# M220C.net
KiCad netlist of a schematic drawn in EAGLE
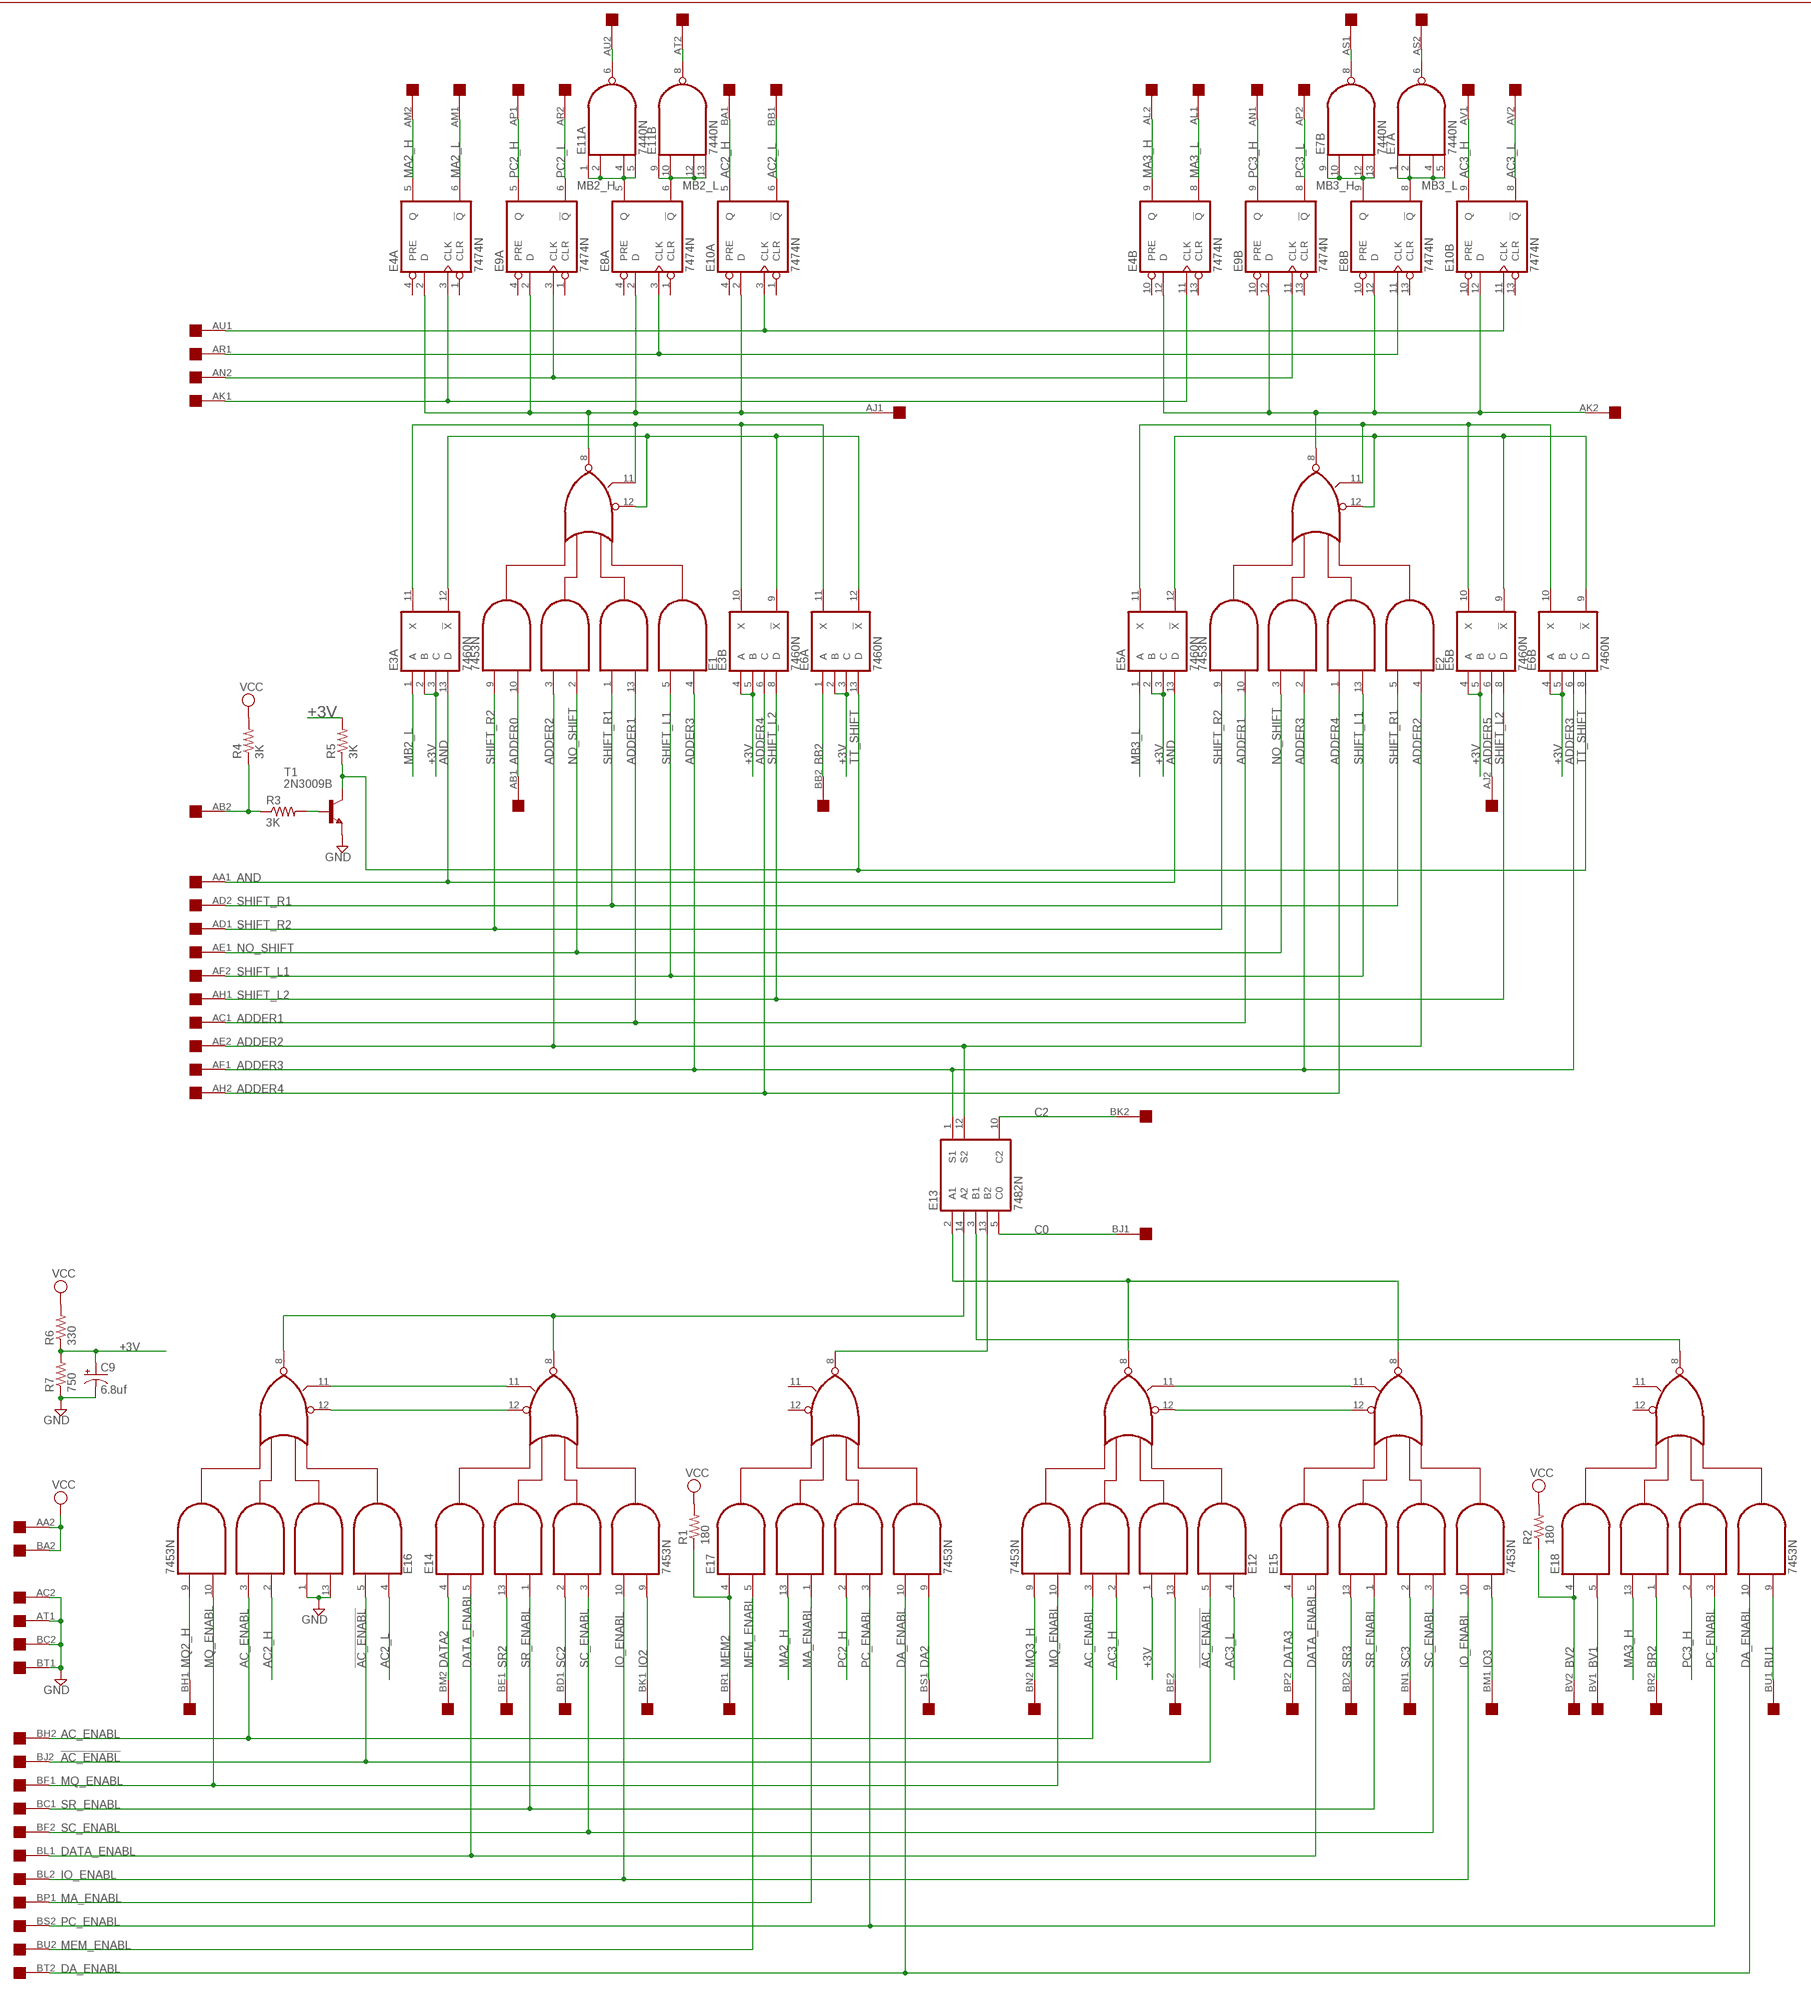
[diagram p0: schematic, sheet 1, part 1 of 2]
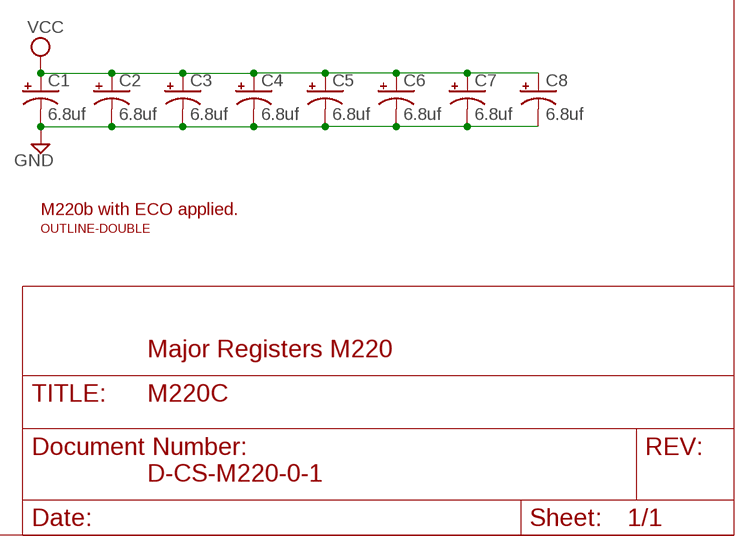
[diagram p1: schematic, sheet 1, part 2 of 2]

(export (version "E")
  (design (tool "Eeschema 10.0.6"))
  (components
    (comp (ref "C1")
      (value "6.8uf")
      (footprint "eagle-import:E15-5")
      (libsource (lib "eagle-import") (part "CPOL-USE15-5AXIAL"))
    )
    (comp (ref "C2")
      (value "6.8uf")
      (footprint "eagle-import:E15-5")
      (libsource (lib "eagle-import") (part "CPOL-USE15-5AXIAL"))
    )
    (comp (ref "C3")
      (value "6.8uf")
      (footprint "eagle-import:E15-5")
      (libsource (lib "eagle-import") (part "CPOL-USE15-5AXIAL"))
    )
    (comp (ref "C4")
      (value "6.8uf")
      (footprint "eagle-import:E15-5")
      (libsource (lib "eagle-import") (part "CPOL-USE15-5AXIAL"))
    )
    (comp (ref "C5")
      (value "6.8uf")
      (footprint "eagle-import:E15-5")
      (libsource (lib "eagle-import") (part "CPOL-USE15-5AXIAL"))
    )
    (comp (ref "C6")
      (value "6.8uf")
      (footprint "eagle-import:E15-5")
      (libsource (lib "eagle-import") (part "CPOL-USE15-5AXIAL"))
    )
    (comp (ref "C7")
      (value "6.8uf")
      (footprint "eagle-import:E15-5")
      (libsource (lib "eagle-import") (part "CPOL-USE15-5AXIAL"))
    )
    (comp (ref "C8")
      (value "6.8uf")
      (footprint "eagle-import:E15-5")
      (libsource (lib "eagle-import") (part "CPOL-USE15-5AXIAL"))
    )
    (comp (ref "C9")
      (value "6.8uf")
      (footprint "eagle-import:E15-5")
      (libsource (lib "eagle-import") (part "CPOL-USE15-5AXIAL"))
    )
    (comp (ref "E1")
      (value "7453N")
      (footprint "eagle-import:DIL14")
      (libsource (lib "eagle-import") (part "7453N"))
    )
    (comp (ref "E2")
      (value "7453N")
      (footprint "eagle-import:DIL14")
      (libsource (lib "eagle-import") (part "7453N"))
    )
    (comp (ref "E3")
      (value "7460N")
      (footprint "eagle-import:DIL14")
      (libsource (lib "eagle-import") (part "7460N"))
    )
    (comp (ref "E4")
      (value "7474N")
      (footprint "eagle-import:DIL14")
      (libsource (lib "eagle-import") (part "7474NS"))
    )
    (comp (ref "E5")
      (value "7460N")
      (footprint "eagle-import:DIL14")
      (libsource (lib "eagle-import") (part "7460N"))
    )
    (comp (ref "E6")
      (value "7460N")
      (footprint "eagle-import:DIL14")
      (libsource (lib "eagle-import") (part "7460N"))
    )
    (comp (ref "E7")
      (value "7440N")
      (footprint "eagle-import:DIL14")
      (libsource (lib "eagle-import") (part "7420NS"))
    )
    (comp (ref "E8")
      (value "7474N")
      (footprint "eagle-import:DIL14")
      (libsource (lib "eagle-import") (part "7474NS"))
    )
    (comp (ref "E9")
      (value "7474N")
      (footprint "eagle-import:DIL14")
      (libsource (lib "eagle-import") (part "7474NS"))
    )
    (comp (ref "E10")
      (value "7474N")
      (footprint "eagle-import:DIL14")
      (libsource (lib "eagle-import") (part "7474NS"))
    )
    (comp (ref "E11")
      (value "7440N")
      (footprint "eagle-import:DIL14")
      (libsource (lib "eagle-import") (part "7420NS"))
    )
    (comp (ref "E12")
      (value "7453N")
      (footprint "eagle-import:DIL14")
      (libsource (lib "eagle-import") (part "7453N"))
    )
    (comp (ref "E13")
      (value "7482N")
      (footprint "eagle-import:DIL14")
      (libsource (lib "eagle-import") (part "7482N"))
    )
    (comp (ref "E14")
      (value "7453N")
      (footprint "eagle-import:DIL14")
      (libsource (lib "eagle-import") (part "7453N"))
    )
    (comp (ref "E15")
      (value "7453N")
      (footprint "eagle-import:DIL14")
      (libsource (lib "eagle-import") (part "7453N"))
    )
    (comp (ref "E16")
      (value "7453N")
      (footprint "eagle-import:DIL14")
      (libsource (lib "eagle-import") (part "7453N"))
    )
    (comp (ref "E17")
      (value "7453N")
      (footprint "eagle-import:DIL14")
      (libsource (lib "eagle-import") (part "7453N"))
    )
    (comp (ref "E18")
      (value "7453N")
      (footprint "eagle-import:DIL14")
      (libsource (lib "eagle-import") (part "7453N"))
    )
    (comp (ref "R1")
      (value "180")
      (footprint "eagle-import:0207_10")
      (libsource (lib "eagle-import") (part "R-US_0207/10"))
    )
    (comp (ref "R2")
      (value "180")
      (footprint "eagle-import:0207_10")
      (libsource (lib "eagle-import") (part "R-US_0207/10"))
    )
    (comp (ref "R3")
      (value "3K")
      (footprint "eagle-import:0207_10")
      (libsource (lib "eagle-import") (part "R-US_0207/10"))
    )
    (comp (ref "R4")
      (value "3K")
      (footprint "eagle-import:0207_10")
      (libsource (lib "eagle-import") (part "R-US_0207/10"))
    )
    (comp (ref "R5")
      (value "3K")
      (footprint "eagle-import:0207_10")
      (libsource (lib "eagle-import") (part "R-US_0207/10"))
    )
    (comp (ref "R6")
      (value "330")
      (footprint "eagle-import:0207_10")
      (libsource (lib "eagle-import") (part "R-US_0207/10"))
    )
    (comp (ref "R7")
      (value "750")
      (footprint "eagle-import:0207_10")
      (libsource (lib "eagle-import") (part "R-US_0207/10"))
    )
    (comp (ref "T1")
      (value "2N3009B")
      (footprint "eagle-import:TO5")
      (libsource (lib "eagle-import") (part "2N1613"))
    )
    (comp (ref "U$1")
      (value "DOUBLE")
      (footprint "eagle-import:EDGE-CON4")
      (libsource (lib "eagle-import") (part "DOUBLE"))
    )
    (comp (ref "U$2")
      (value "OUTLINE-DOUBLE")
      (footprint "eagle-import:DOUBLE")
      (libsource (lib "eagle-import") (part "OUTLINE-DOUBLE"))
    )
  )
  (nets
    (net (code "1") (name "/+3V") (class "Default")
      (node (ref "C9") (pin "+") (pinfunction "+_+") (pintype "passive"))
      (node (ref "E12") (pin "1") (pinfunction "I4_1") (pintype "input"))
      (node (ref "E3") (pin "2") (pinfunction "B_2") (pintype "input"))
      (node (ref "E3") (pin "3") (pinfunction "C_3") (pintype "input"))
      (node (ref "E3") (pin "4") (pinfunction "A_4") (pintype "input"))
      (node (ref "E3") (pin "5") (pinfunction "B_5") (pintype "input"))
      (node (ref "E5") (pin "2") (pinfunction "B_2") (pintype "input"))
      (node (ref "E5") (pin "3") (pinfunction "C_3") (pintype "input"))
      (node (ref "E5") (pin "4") (pinfunction "A_4") (pintype "input"))
      (node (ref "E5") (pin "5") (pinfunction "B_5") (pintype "input"))
      (node (ref "E6") (pin "2") (pinfunction "B_2") (pintype "input"))
      (node (ref "E6") (pin "3") (pinfunction "C_3") (pintype "input"))
      (node (ref "E6") (pin "4") (pinfunction "A_4") (pintype "input"))
      (node (ref "E6") (pin "5") (pinfunction "B_5") (pintype "input"))
      (node (ref "R5") (pin "2") (pinfunction "2_2") (pintype "passive"))
      (node (ref "R6") (pin "1") (pinfunction "1_1") (pintype "passive"))
      (node (ref "R7") (pin "2") (pinfunction "2_2") (pintype "passive"))
    )
    (net (code "2") (name "/AC2_H") (class "Default")
      (node (ref "E10") (pin "5") (pinfunction "Q_5") (pintype "output"))
      (node (ref "E16") (pin "2") (pinfunction "I5_2") (pintype "input"))
      (node (ref "U$1") (pin "BA1") (pinfunction "1_BA1") (pintype "bidirectional"))
    )
    (net (code "3") (name "/AC2_L") (class "Default")
      (node (ref "E10") (pin "6") (pinfunction "~{Q}_6") (pintype "output"))
      (node (ref "E16") (pin "4") (pinfunction "I1_4") (pintype "input"))
      (node (ref "U$1") (pin "BB1") (pinfunction "1_BB1") (pintype "bidirectional"))
    )
    (net (code "4") (name "/AC3_H") (class "Default")
      (node (ref "E10") (pin "9") (pinfunction "Q_9") (pintype "output"))
      (node (ref "E12") (pin "2") (pinfunction "I5_2") (pintype "input"))
      (node (ref "U$1") (pin "AV1") (pinfunction "1_AV1") (pintype "bidirectional"))
    )
    (net (code "5") (name "/AC3_L") (class "Default")
      (node (ref "E10") (pin "8") (pinfunction "~{Q}_8") (pintype "output"))
      (node (ref "E12") (pin "4") (pinfunction "I1_4") (pintype "input"))
      (node (ref "U$1") (pin "AV2") (pinfunction "1_AV2") (pintype "bidirectional"))
    )
    (net (code "6") (name "/AC_ENABL") (class "Default")
      (node (ref "E12") (pin "3") (pinfunction "I6_3") (pintype "input"))
      (node (ref "E16") (pin "3") (pinfunction "I6_3") (pintype "input"))
      (node (ref "U$1") (pin "BH2") (pinfunction "1_BH2") (pintype "bidirectional"))
    )
    (net (code "7") (name "/ADDER0") (class "Default")
      (node (ref "E1") (pin "10") (pinfunction "I7_10") (pintype "input"))
      (node (ref "U$1") (pin "AB1") (pinfunction "1_AB1") (pintype "bidirectional"))
    )
    (net (code "8") (name "/ADDER1") (class "Default")
      (node (ref "E1") (pin "13") (pinfunction "I3_13") (pintype "input"))
      (node (ref "E2") (pin "10") (pinfunction "I7_10") (pintype "input"))
      (node (ref "U$1") (pin "AC1") (pinfunction "1_AC1") (pintype "bidirectional"))
    )
    (net (code "9") (name "/ADDER2") (class "Default")
      (node (ref "E1") (pin "3") (pinfunction "I6_3") (pintype "input"))
      (node (ref "E13") (pin "12") (pinfunction "S2_12") (pintype "output"))
      (node (ref "E2") (pin "4") (pinfunction "I1_4") (pintype "input"))
      (node (ref "U$1") (pin "AE2") (pinfunction "1_AE2") (pintype "bidirectional"))
    )
    (net (code "10") (name "/ADDER3") (class "Default")
      (node (ref "E1") (pin "4") (pinfunction "I1_4") (pintype "input"))
      (node (ref "E13") (pin "1") (pinfunction "S1_1") (pintype "output"))
      (node (ref "E2") (pin "2") (pinfunction "I5_2") (pintype "input"))
      (node (ref "E6") (pin "6") (pinfunction "C_6") (pintype "input"))
      (node (ref "U$1") (pin "AF1") (pinfunction "1_AF1") (pintype "bidirectional"))
    )
    (net (code "11") (name "/ADDER4") (class "Default")
      (node (ref "E2") (pin "1") (pinfunction "I4_1") (pintype "input"))
      (node (ref "E3") (pin "6") (pinfunction "C_6") (pintype "input"))
      (node (ref "U$1") (pin "AH2") (pinfunction "1_AH2") (pintype "bidirectional"))
    )
    (net (code "12") (name "/ADDER5") (class "Default")
      (node (ref "E5") (pin "6") (pinfunction "C_6") (pintype "input"))
      (node (ref "U$1") (pin "AJ2") (pinfunction "1_AJ2") (pintype "bidirectional"))
    )
    (net (code "13") (name "/AND") (class "Default")
      (node (ref "E3") (pin "13") (pinfunction "D_13") (pintype "input"))
      (node (ref "E5") (pin "13") (pinfunction "D_13") (pintype "input"))
      (node (ref "U$1") (pin "AA1") (pinfunction "1_AA1") (pintype "bidirectional"))
    )
    (net (code "14") (name "/BB2") (class "Default")
      (node (ref "E6") (pin "1") (pinfunction "A_1") (pintype "input"))
      (node (ref "U$1") (pin "BB2") (pinfunction "1_BB2") (pintype "bidirectional"))
    )
    (net (code "15") (name "/BR2") (class "Default")
      (node (ref "E18") (pin "1") (pinfunction "I4_1") (pintype "input"))
      (node (ref "U$1") (pin "BR2") (pinfunction "1_BR2") (pintype "bidirectional"))
    )
    (net (code "16") (name "/BU1") (class "Default")
      (node (ref "E18") (pin "9") (pinfunction "I8_9") (pintype "input"))
      (node (ref "U$1") (pin "BU1") (pinfunction "1_BU1") (pintype "bidirectional"))
    )
    (net (code "17") (name "/BV1") (class "Default")
      (node (ref "E18") (pin "5") (pinfunction "I2_5") (pintype "input"))
      (node (ref "U$1") (pin "BV1") (pinfunction "1_BV1") (pintype "bidirectional"))
    )
    (net (code "18") (name "/BV2") (class "Default")
      (node (ref "E18") (pin "4") (pinfunction "I1_4") (pintype "input"))
      (node (ref "R2") (pin "1") (pinfunction "1_1") (pintype "passive"))
      (node (ref "U$1") (pin "BV2") (pinfunction "1_BV2") (pintype "bidirectional"))
    )
    (net (code "19") (name "/C0") (class "Default")
      (node (ref "E13") (pin "5") (pinfunction "C0_5") (pintype "input"))
      (node (ref "U$1") (pin "BJ1") (pinfunction "1_BJ1") (pintype "bidirectional"))
    )
    (net (code "20") (name "/C2") (class "Default")
      (node (ref "E13") (pin "10") (pinfunction "C2_10") (pintype "output"))
      (node (ref "U$1") (pin "BK2") (pinfunction "1_BK2") (pintype "bidirectional"))
    )
    (net (code "21") (name "/DA2") (class "Default")
      (node (ref "E17") (pin "9") (pinfunction "I8_9") (pintype "input"))
      (node (ref "U$1") (pin "BS1") (pinfunction "1_BS1") (pintype "bidirectional"))
    )
    (net (code "22") (name "/DATA2") (class "Default")
      (node (ref "E14") (pin "4") (pinfunction "I1_4") (pintype "input"))
      (node (ref "U$1") (pin "BM2") (pinfunction "1_BM2") (pintype "bidirectional"))
    )
    (net (code "23") (name "/DATA3") (class "Default")
      (node (ref "E15") (pin "4") (pinfunction "I1_4") (pintype "input"))
      (node (ref "U$1") (pin "BP2") (pinfunction "1_BP2") (pintype "bidirectional"))
    )
    (net (code "24") (name "/DATA_ENABL") (class "Default")
      (node (ref "E14") (pin "5") (pinfunction "I2_5") (pintype "input"))
      (node (ref "E15") (pin "5") (pinfunction "I2_5") (pintype "input"))
      (node (ref "U$1") (pin "BL1") (pinfunction "1_BL1") (pintype "bidirectional"))
    )
    (net (code "25") (name "/DA_ENABL") (class "Default")
      (node (ref "E17") (pin "10") (pinfunction "I7_10") (pintype "input"))
      (node (ref "E18") (pin "10") (pinfunction "I7_10") (pintype "input"))
      (node (ref "U$1") (pin "BT2") (pinfunction "1_BT2") (pintype "bidirectional"))
    )
    (net (code "26") (name "/IO2") (class "Default")
      (node (ref "E14") (pin "9") (pinfunction "I8_9") (pintype "input"))
      (node (ref "U$1") (pin "BK1") (pinfunction "1_BK1") (pintype "bidirectional"))
    )
    (net (code "27") (name "/IO3") (class "Default")
      (node (ref "E15") (pin "9") (pinfunction "I8_9") (pintype "input"))
      (node (ref "U$1") (pin "BM1") (pinfunction "1_BM1") (pintype "bidirectional"))
    )
    (net (code "28") (name "/IO_ENABL") (class "Default")
      (node (ref "E14") (pin "10") (pinfunction "I7_10") (pintype "input"))
      (node (ref "E15") (pin "10") (pinfunction "I7_10") (pintype "input"))
      (node (ref "U$1") (pin "BL2") (pinfunction "1_BL2") (pintype "bidirectional"))
    )
    (net (code "29") (name "/MA2_H") (class "Default")
      (node (ref "E17") (pin "13") (pinfunction "I3_13") (pintype "input"))
      (node (ref "E4") (pin "5") (pinfunction "Q_5") (pintype "output"))
      (node (ref "U$1") (pin "AM2") (pinfunction "1_AM2") (pintype "bidirectional"))
    )
    (net (code "30") (name "/MA2_L") (class "Default")
      (node (ref "E4") (pin "6") (pinfunction "~{Q}_6") (pintype "output"))
      (node (ref "U$1") (pin "AM1") (pinfunction "1_AM1") (pintype "bidirectional"))
    )
    (net (code "31") (name "/MA3_H") (class "Default")
      (node (ref "E18") (pin "13") (pinfunction "I3_13") (pintype "input"))
      (node (ref "E4") (pin "9") (pinfunction "Q_9") (pintype "output"))
      (node (ref "U$1") (pin "AL2") (pinfunction "1_AL2") (pintype "bidirectional"))
    )
    (net (code "32") (name "/MA3_L") (class "Default")
      (node (ref "E4") (pin "8") (pinfunction "~{Q}_8") (pintype "output"))
      (node (ref "U$1") (pin "AL1") (pinfunction "1_AL1") (pintype "bidirectional"))
    )
    (net (code "33") (name "/MA_ENABL") (class "Default")
      (node (ref "E17") (pin "1") (pinfunction "I4_1") (pintype "input"))
      (node (ref "U$1") (pin "BP1") (pinfunction "1_BP1") (pintype "bidirectional"))
    )
    (net (code "34") (name "/MB2_H") (class "Default")
      (node (ref "E11") (pin "1") (pinfunction "I0_1") (pintype "input"))
      (node (ref "E11") (pin "2") (pinfunction "I1_2") (pintype "input"))
      (node (ref "E11") (pin "4") (pinfunction "I2_4") (pintype "input"))
      (node (ref "E11") (pin "5") (pinfunction "I3_5") (pintype "input"))
      (node (ref "E8") (pin "5") (pinfunction "Q_5") (pintype "output"))
    )
    (net (code "35") (name "/MB2_L") (class "Default")
      (node (ref "E11") (pin "10") (pinfunction "I1_10") (pintype "input"))
      (node (ref "E11") (pin "12") (pinfunction "I2_12") (pintype "input"))
      (node (ref "E11") (pin "13") (pinfunction "I3_13") (pintype "input"))
      (node (ref "E11") (pin "9") (pinfunction "I0_9") (pintype "input"))
      (node (ref "E3") (pin "1") (pinfunction "A_1") (pintype "input"))
      (node (ref "E8") (pin "6") (pinfunction "~{Q}_6") (pintype "output"))
    )
    (net (code "36") (name "/MB3_H") (class "Default")
      (node (ref "E7") (pin "10") (pinfunction "I1_10") (pintype "input"))
      (node (ref "E7") (pin "12") (pinfunction "I2_12") (pintype "input"))
      (node (ref "E7") (pin "13") (pinfunction "I3_13") (pintype "input"))
      (node (ref "E7") (pin "9") (pinfunction "I0_9") (pintype "input"))
      (node (ref "E8") (pin "9") (pinfunction "Q_9") (pintype "output"))
    )
    (net (code "37") (name "/MB3_L") (class "Default")
      (node (ref "E5") (pin "1") (pinfunction "A_1") (pintype "input"))
      (node (ref "E7") (pin "1") (pinfunction "I0_1") (pintype "input"))
      (node (ref "E7") (pin "2") (pinfunction "I1_2") (pintype "input"))
      (node (ref "E7") (pin "4") (pinfunction "I2_4") (pintype "input"))
      (node (ref "E7") (pin "5") (pinfunction "I3_5") (pintype "input"))
      (node (ref "E8") (pin "8") (pinfunction "~{Q}_8") (pintype "output"))
    )
    (net (code "38") (name "/MEM2") (class "Default")
      (node (ref "E17") (pin "4") (pinfunction "I1_4") (pintype "input"))
      (node (ref "R1") (pin "1") (pinfunction "1_1") (pintype "passive"))
      (node (ref "U$1") (pin "BR1") (pinfunction "1_BR1") (pintype "bidirectional"))
    )
    (net (code "39") (name "/MEM_ENABL") (class "Default")
      (node (ref "E17") (pin "5") (pinfunction "I2_5") (pintype "input"))
      (node (ref "U$1") (pin "BU2") (pinfunction "1_BU2") (pintype "bidirectional"))
    )
    (net (code "40") (name "/MQ2_H") (class "Default")
      (node (ref "E16") (pin "9") (pinfunction "I8_9") (pintype "input"))
      (node (ref "U$1") (pin "BH1") (pinfunction "1_BH1") (pintype "bidirectional"))
    )
    (net (code "41") (name "/MQ3_H") (class "Default")
      (node (ref "E12") (pin "9") (pinfunction "I8_9") (pintype "input"))
      (node (ref "U$1") (pin "BN2") (pinfunction "1_BN2") (pintype "bidirectional"))
    )
    (net (code "42") (name "/MQ_ENABL") (class "Default")
      (node (ref "E12") (pin "10") (pinfunction "I7_10") (pintype "input"))
      (node (ref "E16") (pin "10") (pinfunction "I7_10") (pintype "input"))
      (node (ref "U$1") (pin "BF1") (pinfunction "1_BF1") (pintype "bidirectional"))
    )
    (net (code "43") (name "/NO_SHIFT") (class "Default")
      (node (ref "E1") (pin "2") (pinfunction "I5_2") (pintype "input"))
      (node (ref "E2") (pin "3") (pinfunction "I6_3") (pintype "input"))
      (node (ref "U$1") (pin "AE1") (pinfunction "1_AE1") (pintype "bidirectional"))
    )
    (net (code "44") (name "/PC2_H") (class "Default")
      (node (ref "E17") (pin "2") (pinfunction "I5_2") (pintype "input"))
      (node (ref "E9") (pin "5") (pinfunction "Q_5") (pintype "output"))
      (node (ref "U$1") (pin "AP1") (pinfunction "1_AP1") (pintype "bidirectional"))
    )
    (net (code "45") (name "/PC2_L") (class "Default")
      (node (ref "E9") (pin "6") (pinfunction "~{Q}_6") (pintype "output"))
      (node (ref "U$1") (pin "AR2") (pinfunction "1_AR2") (pintype "bidirectional"))
    )
    (net (code "46") (name "/PC3_H") (class "Default")
      (node (ref "E18") (pin "2") (pinfunction "I5_2") (pintype "input"))
      (node (ref "E9") (pin "9") (pinfunction "Q_9") (pintype "output"))
      (node (ref "U$1") (pin "AN1") (pinfunction "1_AN1") (pintype "bidirectional"))
    )
    (net (code "47") (name "/PC3_L") (class "Default")
      (node (ref "E9") (pin "8") (pinfunction "~{Q}_8") (pintype "output"))
      (node (ref "U$1") (pin "AP2") (pinfunction "1_AP2") (pintype "bidirectional"))
    )
    (net (code "48") (name "/PC_ENABL") (class "Default")
      (node (ref "E17") (pin "3") (pinfunction "I6_3") (pintype "input"))
      (node (ref "E18") (pin "3") (pinfunction "I6_3") (pintype "input"))
      (node (ref "U$1") (pin "BS2") (pinfunction "1_BS2") (pintype "bidirectional"))
    )
    (net (code "49") (name "/SC2") (class "Default")
      (node (ref "E14") (pin "2") (pinfunction "I5_2") (pintype "input"))
      (node (ref "U$1") (pin "BD1") (pinfunction "1_BD1") (pintype "bidirectional"))
    )
    (net (code "50") (name "/SC3") (class "Default")
      (node (ref "E15") (pin "2") (pinfunction "I5_2") (pintype "input"))
      (node (ref "U$1") (pin "BN1") (pinfunction "1_BN1") (pintype "bidirectional"))
    )
    (net (code "51") (name "/SC_ENABL") (class "Default")
      (node (ref "E14") (pin "3") (pinfunction "I6_3") (pintype "input"))
      (node (ref "E15") (pin "3") (pinfunction "I6_3") (pintype "input"))
      (node (ref "U$1") (pin "BF2") (pinfunction "1_BF2") (pintype "bidirectional"))
    )
    (net (code "52") (name "/SHIFT_L1") (class "Default")
      (node (ref "E1") (pin "5") (pinfunction "I2_5") (pintype "input"))
      (node (ref "E2") (pin "13") (pinfunction "I3_13") (pintype "input"))
      (node (ref "U$1") (pin "AF2") (pinfunction "1_AF2") (pintype "bidirectional"))
    )
    (net (code "53") (name "/SHIFT_L2") (class "Default")
      (node (ref "E3") (pin "8") (pinfunction "D_8") (pintype "input"))
      (node (ref "E5") (pin "8") (pinfunction "D_8") (pintype "input"))
      (node (ref "U$1") (pin "AH1") (pinfunction "1_AH1") (pintype "bidirectional"))
    )
    (net (code "54") (name "/SHIFT_R1") (class "Default")
      (node (ref "E1") (pin "1") (pinfunction "I4_1") (pintype "input"))
      (node (ref "E2") (pin "5") (pinfunction "I2_5") (pintype "input"))
      (node (ref "U$1") (pin "AD2") (pinfunction "1_AD2") (pintype "bidirectional"))
    )
    (net (code "55") (name "/SHIFT_R2") (class "Default")
      (node (ref "E1") (pin "9") (pinfunction "I8_9") (pintype "input"))
      (node (ref "E2") (pin "9") (pinfunction "I8_9") (pintype "input"))
      (node (ref "U$1") (pin "AD1") (pinfunction "1_AD1") (pintype "bidirectional"))
    )
    (net (code "56") (name "/SR2") (class "Default")
      (node (ref "E14") (pin "13") (pinfunction "I3_13") (pintype "input"))
      (node (ref "U$1") (pin "BE1") (pinfunction "1_BE1") (pintype "bidirectional"))
    )
    (net (code "57") (name "/SR3") (class "Default")
      (node (ref "E15") (pin "13") (pinfunction "I3_13") (pintype "input"))
      (node (ref "U$1") (pin "BD2") (pinfunction "1_BD2") (pintype "bidirectional"))
    )
    (net (code "58") (name "/SR_ENABL") (class "Default")
      (node (ref "E14") (pin "1") (pinfunction "I4_1") (pintype "input"))
      (node (ref "E15") (pin "1") (pinfunction "I4_1") (pintype "input"))
      (node (ref "U$1") (pin "BC1") (pinfunction "1_BC1") (pintype "bidirectional"))
    )
    (net (code "59") (name "/TT_SHIFT") (class "Default")
      (node (ref "E6") (pin "13") (pinfunction "D_13") (pintype "input"))
      (node (ref "E6") (pin "8") (pinfunction "D_8") (pintype "input"))
      (node (ref "R5") (pin "1") (pinfunction "1_1") (pintype "passive"))
      (node (ref "T1") (pin "3") (pinfunction "C_3") (pintype "passive"))
    )
    (net (code "60") (name "/~{AC_ENABL}") (class "Default")
      (node (ref "E12") (pin "5") (pinfunction "I2_5") (pintype "input"))
      (node (ref "E16") (pin "5") (pinfunction "I2_5") (pintype "input"))
      (node (ref "U$1") (pin "BJ2") (pinfunction "1_BJ2") (pintype "bidirectional"))
    )
    (net (code "61") (name "GND") (class "Default")
      (node (ref "C1") (pin "-") (pinfunction "-_-") (pintype "passive"))
      (node (ref "C2") (pin "-") (pinfunction "-_-") (pintype "passive"))
      (node (ref "C3") (pin "-") (pinfunction "-_-") (pintype "passive"))
      (node (ref "C4") (pin "-") (pinfunction "-_-") (pintype "passive"))
      (node (ref "C5") (pin "-") (pinfunction "-_-") (pintype "passive"))
      (node (ref "C6") (pin "-") (pinfunction "-_-") (pintype "passive"))
      (node (ref "C7") (pin "-") (pinfunction "-_-") (pintype "passive"))
      (node (ref "C8") (pin "-") (pinfunction "-_-") (pintype "passive"))
      (node (ref "C9") (pin "-") (pinfunction "-_-") (pintype "passive"))
      (node (ref "E16") (pin "1") (pinfunction "I4_1") (pintype "input"))
      (node (ref "E16") (pin "13") (pinfunction "I3_13") (pintype "input"))
      (node (ref "R7") (pin "1") (pinfunction "1_1") (pintype "passive"))
      (node (ref "T1") (pin "1") (pinfunction "E_1") (pintype "passive"))
      (node (ref "U$1") (pin "AC2") (pinfunction "1_AC2") (pintype "bidirectional"))
      (node (ref "U$1") (pin "AT1") (pinfunction "1_AT1") (pintype "bidirectional"))
      (node (ref "U$1") (pin "BC2") (pinfunction "1_BC2") (pintype "bidirectional"))
      (node (ref "U$1") (pin "BT1") (pinfunction "1_BT1") (pintype "bidirectional"))
    )
    (net (code "62") (name "Net-(E1A-I9)") (class "Default")
      (node (ref "E1") (pin "12") (pinfunction "I9_12") (pintype "passive"))
      (node (ref "E3") (pin "12") (pinfunction "~{X}_12") (pintype "output"))
      (node (ref "E3") (pin "9") (pinfunction "~{X}_9") (pintype "output"))
      (node (ref "E6") (pin "12") (pinfunction "~{X}_12") (pintype "output"))
    )
    (net (code "63") (name "Net-(E1A-I10)") (class "Default")
      (node (ref "E1") (pin "11") (pinfunction "I10_11") (pintype "passive"))
      (node (ref "E3") (pin "10") (pinfunction "X_10") (pintype "output"))
      (node (ref "E3") (pin "11") (pinfunction "X_11") (pintype "output"))
      (node (ref "E6") (pin "11") (pinfunction "X_11") (pintype "output"))
    )
    (net (code "64") (name "Net-(E2A-I9)") (class "Default")
      (node (ref "E2") (pin "12") (pinfunction "I9_12") (pintype "passive"))
      (node (ref "E5") (pin "12") (pinfunction "~{X}_12") (pintype "output"))
      (node (ref "E5") (pin "9") (pinfunction "~{X}_9") (pintype "output"))
      (node (ref "E6") (pin "9") (pinfunction "~{X}_9") (pintype "output"))
    )
    (net (code "65") (name "Net-(E2A-I10)") (class "Default")
      (node (ref "E2") (pin "11") (pinfunction "I10_11") (pintype "passive"))
      (node (ref "E5") (pin "10") (pinfunction "X_10") (pintype "output"))
      (node (ref "E5") (pin "11") (pinfunction "X_11") (pintype "output"))
      (node (ref "E6") (pin "10") (pinfunction "X_10") (pintype "output"))
    )
    (net (code "66") (name "Net-(E4A-CLK)") (class "Default")
      (node (ref "E4") (pin "11") (pinfunction "CLK_11") (pintype "input"))
      (node (ref "E4") (pin "3") (pinfunction "CLK_3") (pintype "input"))
      (node (ref "U$1") (pin "AK1") (pinfunction "1_AK1") (pintype "bidirectional"))
    )
    (net (code "67") (name "Net-(E7A-O)") (class "Default")
      (node (ref "E7") (pin "6") (pinfunction "O_6") (pintype "output"))
      (node (ref "U$1") (pin "AS2") (pinfunction "1_AS2") (pintype "bidirectional"))
    )
    (net (code "68") (name "Net-(E7B-O)") (class "Default")
      (node (ref "E7") (pin "8") (pinfunction "O_8") (pintype "output"))
      (node (ref "U$1") (pin "AS1") (pinfunction "1_AS1") (pintype "bidirectional"))
    )
    (net (code "69") (name "Net-(E8A-CLK)") (class "Default")
      (node (ref "E8") (pin "11") (pinfunction "CLK_11") (pintype "input"))
      (node (ref "E8") (pin "3") (pinfunction "CLK_3") (pintype "input"))
      (node (ref "U$1") (pin "AR1") (pinfunction "1_AR1") (pintype "bidirectional"))
    )
    (net (code "70") (name "Net-(E9A-CLK)") (class "Default")
      (node (ref "E9") (pin "11") (pinfunction "CLK_11") (pintype "input"))
      (node (ref "E9") (pin "3") (pinfunction "CLK_3") (pintype "input"))
      (node (ref "U$1") (pin "AN2") (pinfunction "1_AN2") (pintype "bidirectional"))
    )
    (net (code "71") (name "Net-(E10A-CLK)") (class "Default")
      (node (ref "E10") (pin "11") (pinfunction "CLK_11") (pintype "input"))
      (node (ref "E10") (pin "3") (pinfunction "CLK_3") (pintype "input"))
      (node (ref "U$1") (pin "AU1") (pinfunction "1_AU1") (pintype "bidirectional"))
    )
    (net (code "72") (name "Net-(E10A-D)") (class "Default")
      (node (ref "E1") (pin "8") (pinfunction "O_8") (pintype "output"))
      (node (ref "E10") (pin "2") (pinfunction "D_2") (pintype "input"))
      (node (ref "E4") (pin "2") (pinfunction "D_2") (pintype "input"))
      (node (ref "E8") (pin "2") (pinfunction "D_2") (pintype "input"))
      (node (ref "E9") (pin "2") (pinfunction "D_2") (pintype "input"))
      (node (ref "U$1") (pin "AJ1") (pinfunction "1_AJ1") (pintype "bidirectional"))
    )
    (net (code "73") (name "Net-(E10B-D)") (class "Default")
      (node (ref "E10") (pin "12") (pinfunction "D_12") (pintype "input"))
      (node (ref "E2") (pin "8") (pinfunction "O_8") (pintype "output"))
      (node (ref "E4") (pin "12") (pinfunction "D_12") (pintype "input"))
      (node (ref "E8") (pin "12") (pinfunction "D_12") (pintype "input"))
      (node (ref "E9") (pin "12") (pinfunction "D_12") (pintype "input"))
      (node (ref "U$1") (pin "AK2") (pinfunction "1_AK2") (pintype "bidirectional"))
    )
    (net (code "74") (name "Net-(E11A-O)") (class "Default")
      (node (ref "E11") (pin "6") (pinfunction "O_6") (pintype "output"))
      (node (ref "U$1") (pin "AU2") (pinfunction "1_AU2") (pintype "bidirectional"))
    )
    (net (code "75") (name "Net-(E11B-O)") (class "Default")
      (node (ref "E11") (pin "8") (pinfunction "O_8") (pintype "output"))
      (node (ref "U$1") (pin "AT2") (pinfunction "1_AT2") (pintype "bidirectional"))
    )
    (net (code "76") (name "Net-(E12A-I3)") (class "Default")
      (node (ref "E12") (pin "13") (pinfunction "I3_13") (pintype "input"))
      (node (ref "U$1") (pin "BE2") (pinfunction "1_BE2") (pintype "bidirectional"))
    )
    (net (code "77") (name "Net-(E12A-I9)") (class "Default")
      (node (ref "E12") (pin "12") (pinfunction "I9_12") (pintype "passive"))
      (node (ref "E15") (pin "12") (pinfunction "I9_12") (pintype "passive"))
    )
    (net (code "78") (name "Net-(E12A-I10)") (class "Default")
      (node (ref "E12") (pin "11") (pinfunction "I10_11") (pintype "passive"))
      (node (ref "E15") (pin "11") (pinfunction "I10_11") (pintype "passive"))
    )
    (net (code "79") (name "Net-(E12A-O)") (class "Default")
      (node (ref "E12") (pin "8") (pinfunction "O_8") (pintype "output"))
      (node (ref "E13") (pin "2") (pinfunction "A1_2") (pintype "input"))
      (node (ref "E15") (pin "8") (pinfunction "O_8") (pintype "output"))
    )
    (net (code "80") (name "Net-(E13E-A2)") (class "Default")
      (node (ref "E13") (pin "14") (pinfunction "A2_14") (pintype "input"))
      (node (ref "E14") (pin "8") (pinfunction "O_8") (pintype "output"))
      (node (ref "E16") (pin "8") (pinfunction "O_8") (pintype "output"))
    )
    (net (code "81") (name "Net-(E13E-B1)") (class "Default")
      (node (ref "E13") (pin "3") (pinfunction "B1_3") (pintype "input"))
      (node (ref "E18") (pin "8") (pinfunction "O_8") (pintype "output"))
    )
    (net (code "82") (name "Net-(E13E-B2)") (class "Default")
      (node (ref "E13") (pin "13") (pinfunction "B2_13") (pintype "input"))
      (node (ref "E17") (pin "8") (pinfunction "O_8") (pintype "output"))
    )
    (net (code "83") (name "Net-(E14A-I9)") (class "Default")
      (node (ref "E14") (pin "12") (pinfunction "I9_12") (pintype "passive"))
      (node (ref "E16") (pin "12") (pinfunction "I9_12") (pintype "passive"))
    )
    (net (code "84") (name "Net-(E14A-I10)") (class "Default")
      (node (ref "E14") (pin "11") (pinfunction "I10_11") (pintype "passive"))
      (node (ref "E16") (pin "11") (pinfunction "I10_11") (pintype "passive"))
    )
    (net (code "85") (name "Net-(T1-B)") (class "Default")
      (node (ref "R3") (pin "2") (pinfunction "2_2") (pintype "passive"))
      (node (ref "T1") (pin "2") (pinfunction "B_2") (pintype "passive"))
    )
    (net (code "86") (name "Net-(U$1D-1)") (class "Default")
      (node (ref "R3") (pin "1") (pinfunction "1_1") (pintype "passive"))
      (node (ref "R4") (pin "1") (pinfunction "1_1") (pintype "passive"))
      (node (ref "U$1") (pin "AB2") (pinfunction "1_AB2") (pintype "bidirectional"))
    )
    (net (code "87") (name "VCC") (class "Default")
      (node (ref "C1") (pin "+") (pinfunction "+_+") (pintype "passive"))
      (node (ref "C2") (pin "+") (pinfunction "+_+") (pintype "passive"))
      (node (ref "C3") (pin "+") (pinfunction "+_+") (pintype "passive"))
      (node (ref "C4") (pin "+") (pinfunction "+_+") (pintype "passive"))
      (node (ref "C5") (pin "+") (pinfunction "+_+") (pintype "passive"))
      (node (ref "C6") (pin "+") (pinfunction "+_+") (pintype "passive"))
      (node (ref "C7") (pin "+") (pinfunction "+_+") (pintype "passive"))
      (node (ref "C8") (pin "+") (pinfunction "+_+") (pintype "passive"))
      (node (ref "R1") (pin "2") (pinfunction "2_2") (pintype "passive"))
      (node (ref "R2") (pin "2") (pinfunction "2_2") (pintype "passive"))
      (node (ref "R4") (pin "2") (pinfunction "2_2") (pintype "passive"))
      (node (ref "R6") (pin "2") (pinfunction "2_2") (pintype "passive"))
      (node (ref "U$1") (pin "AA2") (pinfunction "1_AA2") (pintype "bidirectional"))
      (node (ref "U$1") (pin "BA2") (pinfunction "1_BA2") (pintype "bidirectional"))
    )
    (net (code "88") (name "unconnected-(E4A-CLR-Pad1)") (class "Default")
      (node (ref "E4") (pin "1") (pinfunction "CLR_1") (pintype "input"))
    )
    (net (code "89") (name "unconnected-(E4A-PRE-Pad4)") (class "Default")
      (node (ref "E4") (pin "4") (pinfunction "PRE_4") (pintype "input"))
    )
    (net (code "90") (name "unconnected-(E4B-CLR-Pad13)") (class "Default")
      (node (ref "E4") (pin "13") (pinfunction "CLR_13") (pintype "input"))
    )
    (net (code "91") (name "unconnected-(E4B-PRE-Pad10)") (class "Default")
      (node (ref "E4") (pin "10") (pinfunction "PRE_10") (pintype "input"))
    )
    (net (code "92") (name "unconnected-(E8A-CLR-Pad1)") (class "Default")
      (node (ref "E8") (pin "1") (pinfunction "CLR_1") (pintype "input"))
    )
    (net (code "93") (name "unconnected-(E8A-PRE-Pad4)") (class "Default")
      (node (ref "E8") (pin "4") (pinfunction "PRE_4") (pintype "input"))
    )
    (net (code "94") (name "unconnected-(E8B-CLR-Pad13)") (class "Default")
      (node (ref "E8") (pin "13") (pinfunction "CLR_13") (pintype "input"))
    )
    (net (code "95") (name "unconnected-(E8B-PRE-Pad10)") (class "Default")
      (node (ref "E8") (pin "10") (pinfunction "PRE_10") (pintype "input"))
    )
    (net (code "96") (name "unconnected-(E9A-CLR-Pad1)") (class "Default")
      (node (ref "E9") (pin "1") (pinfunction "CLR_1") (pintype "input"))
    )
    (net (code "97") (name "unconnected-(E9A-PRE-Pad4)") (class "Default")
      (node (ref "E9") (pin "4") (pinfunction "PRE_4") (pintype "input"))
    )
    (net (code "98") (name "unconnected-(E9B-CLR-Pad13)") (class "Default")
      (node (ref "E9") (pin "13") (pinfunction "CLR_13") (pintype "input"))
    )
    (net (code "99") (name "unconnected-(E9B-PRE-Pad10)") (class "Default")
      (node (ref "E9") (pin "10") (pinfunction "PRE_10") (pintype "input"))
    )
    (net (code "100") (name "unconnected-(E10A-CLR-Pad1)") (class "Default")
      (node (ref "E10") (pin "1") (pinfunction "CLR_1") (pintype "input"))
    )
    (net (code "101") (name "unconnected-(E10A-PRE-Pad4)") (class "Default")
      (node (ref "E10") (pin "4") (pinfunction "PRE_4") (pintype "input"))
    )
    (net (code "102") (name "unconnected-(E10B-CLR-Pad13)") (class "Default")
      (node (ref "E10") (pin "13") (pinfunction "CLR_13") (pintype "input"))
    )
    (net (code "103") (name "unconnected-(E10B-PRE-Pad10)") (class "Default")
      (node (ref "E10") (pin "10") (pinfunction "PRE_10") (pintype "input"))
    )
    (net (code "104") (name "unconnected-(E17A-I9-Pad12)") (class "Default")
      (node (ref "E17") (pin "12") (pinfunction "I9_12") (pintype "passive"))
    )
    (net (code "105") (name "unconnected-(E17A-I10-Pad11)") (class "Default")
      (node (ref "E17") (pin "11") (pinfunction "I10_11") (pintype "passive"))
    )
    (net (code "106") (name "unconnected-(E18A-I9-Pad12)") (class "Default")
      (node (ref "E18") (pin "12") (pinfunction "I9_12") (pintype "passive"))
    )
    (net (code "107") (name "unconnected-(E18A-I10-Pad11)") (class "Default")
      (node (ref "E18") (pin "11") (pinfunction "I10_11") (pintype "passive"))
    )
  )
)
